# MCU.net
KiCad netlist of a schematic drawn in Altium Designer
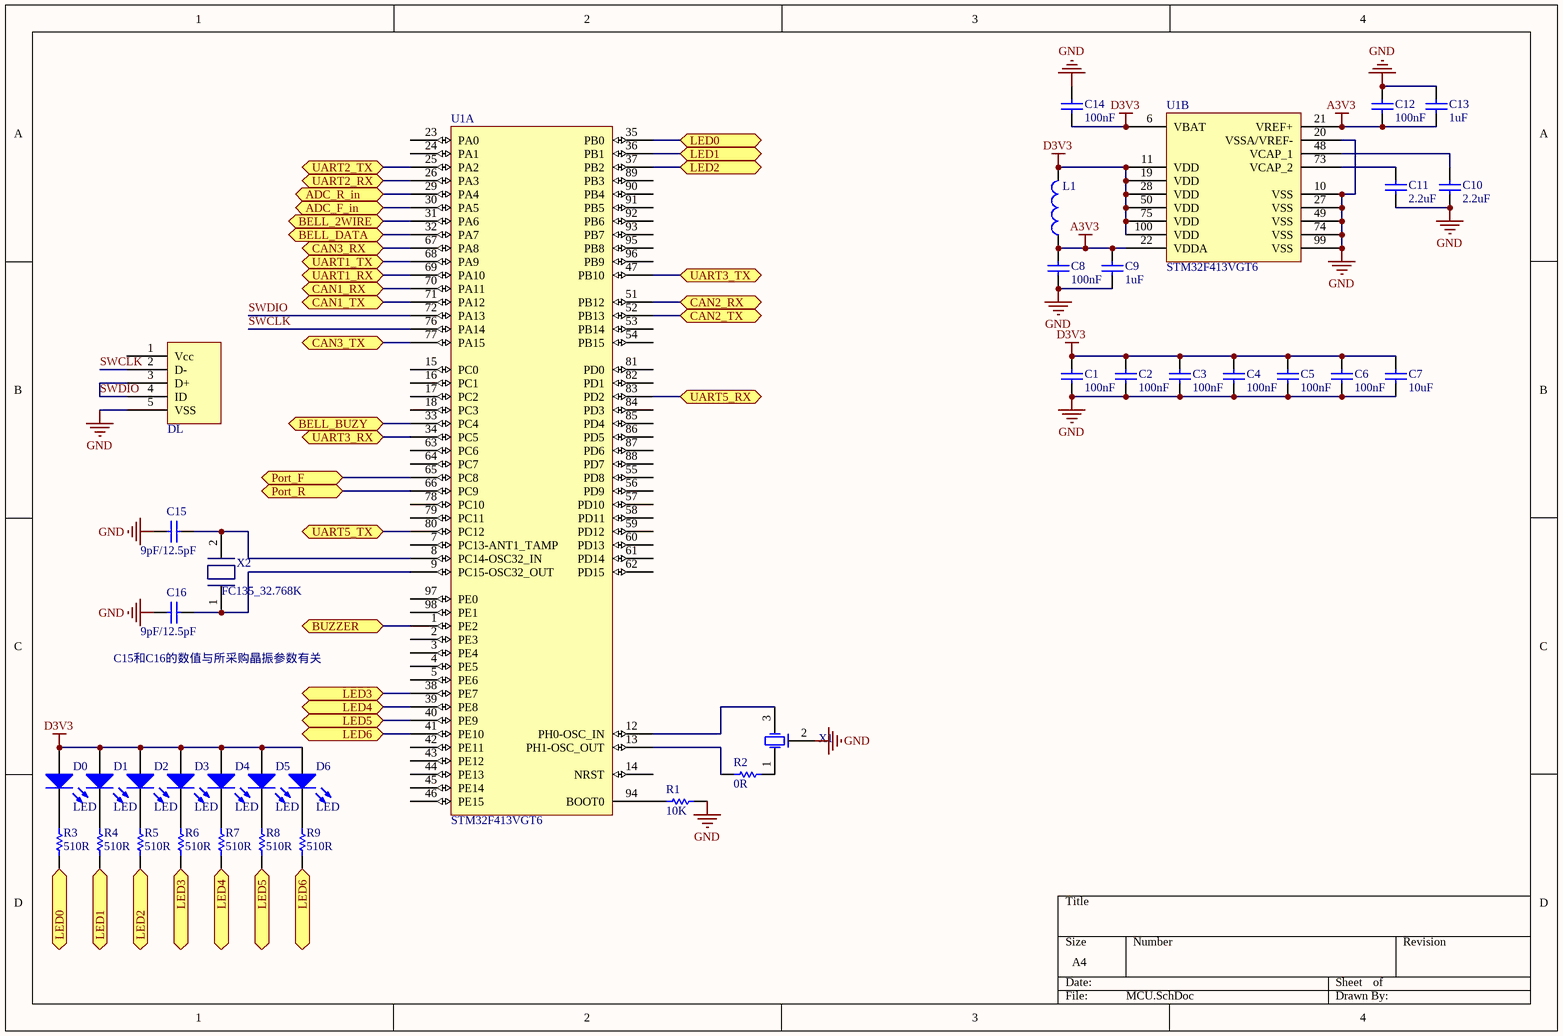
[diagram p0: MCU.SchDoc]

(export (version "E")
  (design (tool "Eeschema 10.0.6"))
  (components
    (comp (ref "C1")
      (value "100nF")
      (footprint "BinFeng:0402")
      (description "Capacitor")
      (fields (field (name "PUBLISHER") "Altium Limited"))
      (libsource (lib "Miscellaneous Devices") (part "Cap"))
    )
    (comp (ref "C2")
      (value "100nF")
      (footprint "BinFeng:0402")
      (description "Capacitor")
      (fields (field (name "PUBLISHER") "Altium Limited"))
      (libsource (lib "Miscellaneous Devices") (part "Cap"))
    )
    (comp (ref "C3")
      (value "100nF")
      (footprint "BinFeng:0402")
      (description "Capacitor")
      (fields (field (name "PUBLISHER") "Altium Limited"))
      (libsource (lib "Miscellaneous Devices") (part "Cap"))
    )
    (comp (ref "C4")
      (value "100nF")
      (footprint "BinFeng:0402")
      (description "Capacitor")
      (fields (field (name "PUBLISHER") "Altium Limited"))
      (libsource (lib "Miscellaneous Devices") (part "Cap"))
    )
    (comp (ref "C5")
      (value "100nF")
      (footprint "BinFeng:0402")
      (description "Capacitor")
      (fields (field (name "PUBLISHER") "Altium Limited"))
      (libsource (lib "Miscellaneous Devices") (part "Cap"))
    )
    (comp (ref "C6")
      (value "100nF")
      (footprint "BinFeng:0402")
      (description "Capacitor")
      (fields (field (name "PUBLISHER") "Altium Limited"))
      (libsource (lib "Miscellaneous Devices") (part "Cap"))
    )
    (comp (ref "C7")
      (value "10uF")
      (footprint "0805")
      (description "Capacitor")
      (fields (field (name "PUBLISHER") "Altium Limited"))
      (libsource (lib "Miscellaneous Devices") (part "Cap"))
    )
    (comp (ref "C8")
      (value "100nF")
      (footprint "BinFeng:0402")
      (description "Capacitor")
      (fields (field (name "PUBLISHER") "Altium Limited"))
      (libsource (lib "Miscellaneous Devices") (part "Cap"))
    )
    (comp (ref "C9")
      (value "1uF")
      (footprint "BinFeng:0402")
      (description "Capacitor")
      (fields (field (name "PUBLISHER") "Altium Limited"))
      (libsource (lib "Miscellaneous Devices") (part "Cap"))
    )
    (comp (ref "C10")
      (value "2.2uF")
      (footprint "BinFeng:0603")
      (description "Capacitor")
      (fields (field (name "PUBLISHER") "Altium Limited"))
      (libsource (lib "Miscellaneous Devices") (part "Cap"))
    )
    (comp (ref "C11")
      (value "2.2uF")
      (footprint "BinFeng:0603")
      (description "Capacitor")
      (fields (field (name "PUBLISHER") "Altium Limited"))
      (libsource (lib "Miscellaneous Devices") (part "Cap"))
    )
    (comp (ref "C12")
      (value "100nF")
      (footprint "BinFeng:0402")
      (description "Capacitor")
      (fields (field (name "PUBLISHER") "Altium Limited"))
      (libsource (lib "Miscellaneous Devices") (part "Cap"))
    )
    (comp (ref "C13")
      (value "1uF")
      (footprint "BinFeng:0402")
      (description "Capacitor")
      (fields (field (name "PUBLISHER") "Altium Limited"))
      (libsource (lib "Miscellaneous Devices") (part "Cap"))
    )
    (comp (ref "C14")
      (value "100nF")
      (footprint "BinFeng:0402")
      (description "Capacitor")
      (fields (field (name "PUBLISHER") "Altium Limited"))
      (libsource (lib "Miscellaneous Devices") (part "Cap"))
    )
    (comp (ref "C15")
      (value "9pF/12.5pF")
      (footprint "BinFeng:0402")
      (description "Capacitor")
      (fields (field (name "PUBLISHER") "Altium Limited"))
      (libsource (lib "Miscellaneous Devices") (part "Cap"))
    )
    (comp (ref "C16")
      (value "9pF/12.5pF")
      (footprint "BinFeng:0402")
      (description "Capacitor")
      (fields (field (name "PUBLISHER") "Altium Limited"))
      (libsource (lib "Miscellaneous Devices") (part "Cap"))
    )
    (comp (ref "D0")
      (value "LED")
      (footprint "1206")
      (description "green LED")
      (fields (field (name "PUBLISHER") "Altium Limited"))
      (libsource (lib "Miscellaneous Devices") (part "LED0"))
    )
    (comp (ref "D1")
      (value "LED")
      (footprint "1206")
      (description "green LED")
      (fields (field (name "PUBLISHER") "Altium Limited"))
      (libsource (lib "Miscellaneous Devices") (part "LED0"))
    )
    (comp (ref "D2")
      (value "LED")
      (footprint "1206")
      (description "green LED")
      (fields (field (name "PUBLISHER") "Altium Limited"))
      (libsource (lib "Miscellaneous Devices") (part "LED0"))
    )
    (comp (ref "D3")
      (value "LED")
      (footprint "1206")
      (description "green LED")
      (fields (field (name "PUBLISHER") "Altium Limited"))
      (libsource (lib "Miscellaneous Devices") (part "LED0"))
    )
    (comp (ref "D4")
      (value "LED")
      (footprint "1206")
      (description "green LED")
      (fields (field (name "PUBLISHER") "Altium Limited"))
      (libsource (lib "Miscellaneous Devices") (part "LED0"))
    )
    (comp (ref "D5")
      (value "LED")
      (footprint "1206")
      (description "green LED")
      (fields (field (name "PUBLISHER") "Altium Limited"))
      (libsource (lib "Miscellaneous Devices") (part "LED0"))
    )
    (comp (ref "D6")
      (value "LED")
      (footprint "1206")
      (description "green LED")
      (fields (field (name "PUBLISHER") "Altium Limited"))
      (libsource (lib "Miscellaneous Devices") (part "LED0"))
    )
    (comp (ref "DL")
      (value "USB_5pin")
      (footprint "USBmicro_B")
      (libsource (lib "BinFeng_Connectors") (part "USB_5pin"))
    )
    (comp (ref "L1")
      (value "BLM15BD221SN1D")
      (footprint "BinFeng:0402")
      (description "muRata ferrite bead")
      (fields (field (name "PUBLISHER") "Altium Limited"))
      (libsource (lib "Miscellaneous Devices") (part "Inductor"))
    )
    (comp (ref "R1")
      (value "10K")
      (footprint "BinFeng:0402")
      (description "Resistor")
      (fields (field (name "PUBLISHER") "Altium Limited"))
      (libsource (lib "Miscellaneous Devices") (part "Res1"))
    )
    (comp (ref "R2")
      (value "0R")
      (footprint "BinFeng:0402")
      (description "Resistor")
      (fields (field (name "PUBLISHER") "Altium Limited"))
      (libsource (lib "Miscellaneous Devices") (part "Res1"))
    )
    (comp (ref "R3")
      (value "510R")
      (footprint "BinFeng:0402")
      (description "Resistor")
      (fields (field (name "PUBLISHER") "Altium Limited"))
      (libsource (lib "Miscellaneous Devices") (part "Res1"))
    )
    (comp (ref "R4")
      (value "510R")
      (footprint "BinFeng:0402")
      (description "Resistor")
      (fields (field (name "PUBLISHER") "Altium Limited"))
      (libsource (lib "Miscellaneous Devices") (part "Res1"))
    )
    (comp (ref "R5")
      (value "510R")
      (footprint "BinFeng:0402")
      (description "Resistor")
      (fields (field (name "PUBLISHER") "Altium Limited"))
      (libsource (lib "Miscellaneous Devices") (part "Res1"))
    )
    (comp (ref "R6")
      (value "510R")
      (footprint "BinFeng:0402")
      (description "Resistor")
      (fields (field (name "PUBLISHER") "Altium Limited"))
      (libsource (lib "Miscellaneous Devices") (part "Res1"))
    )
    (comp (ref "R7")
      (value "510R")
      (footprint "BinFeng:0402")
      (description "Resistor")
      (fields (field (name "PUBLISHER") "Altium Limited"))
      (libsource (lib "Miscellaneous Devices") (part "Res1"))
    )
    (comp (ref "R8")
      (value "510R")
      (footprint "BinFeng:0402")
      (description "Resistor")
      (fields (field (name "PUBLISHER") "Altium Limited"))
      (libsource (lib "Miscellaneous Devices") (part "Res1"))
    )
    (comp (ref "R9")
      (value "510R")
      (footprint "BinFeng:0402")
      (description "Resistor")
      (fields (field (name "PUBLISHER") "Altium Limited"))
      (libsource (lib "Miscellaneous Devices") (part "Res1"))
    )
    (comp (ref "U1")
      (value "STM32F413VGT6")
      (footprint "STM-LQFP100_V")
      (description "ARM Cortex-M4 32-Bit DSP+FPU, 1024 KB Flash, 82 I/Os, 100-Pin LQFP, -40 to 85 degC, Tray")
      (libsource (lib "Altium Content Vault") (part "STM-STM32F413-LQFP-100"))
    )
    (comp (ref "X1")
      (value "8M smd")
      (footprint "8Mhz_XTAL")
      (description "muRata")
      (libsource (lib "Schlib1") (part "8M smd"))
    )
    (comp (ref "X2")
      (value "FC135_32.768K")
      (footprint "FC135")
      (libsource (lib "BinFeng_IC") (part "XTAL_32.768k"))
    )
  )
  (nets
    (net (code "1") (name "/ADC_F_in") (class "Default")
      (node (ref "U1") (pin "30") (pinfunction "PA5_30") (pintype "bidirectional"))
    )
    (net (code "2") (name "/ADC_R_in") (class "Default")
      (node (ref "U1") (pin "29") (pinfunction "PA4_29") (pintype "bidirectional"))
    )
    (net (code "3") (name "/BELL_2WIRE") (class "Default")
      (node (ref "U1") (pin "31") (pinfunction "PA6_31") (pintype "bidirectional"))
    )
    (net (code "4") (name "/BELL_BUZY") (class "Default")
      (node (ref "U1") (pin "33") (pinfunction "PC4_33") (pintype "bidirectional"))
    )
    (net (code "5") (name "/BELL_DATA") (class "Default")
      (node (ref "U1") (pin "32") (pinfunction "PA7_32") (pintype "bidirectional"))
    )
    (net (code "6") (name "/BUZZER") (class "Default")
      (node (ref "U1") (pin "1") (pinfunction "PE2_1") (pintype "bidirectional"))
    )
    (net (code "7") (name "/CAN1_RX") (class "Default")
      (node (ref "U1") (pin "70") (pinfunction "PA11_70") (pintype "bidirectional"))
    )
    (net (code "8") (name "/CAN1_TX") (class "Default")
      (node (ref "U1") (pin "71") (pinfunction "PA12_71") (pintype "bidirectional"))
    )
    (net (code "9") (name "/CAN2_RX") (class "Default")
      (node (ref "U1") (pin "51") (pinfunction "PB12_51") (pintype "bidirectional"))
    )
    (net (code "10") (name "/CAN2_TX") (class "Default")
      (node (ref "U1") (pin "52") (pinfunction "PB13_52") (pintype "bidirectional"))
    )
    (net (code "11") (name "/CAN3_RX") (class "Default")
      (node (ref "U1") (pin "67") (pinfunction "PA8_67") (pintype "bidirectional"))
    )
    (net (code "12") (name "/CAN3_TX") (class "Default")
      (node (ref "U1") (pin "77") (pinfunction "PA15_77") (pintype "bidirectional"))
    )
    (net (code "13") (name "/LED0") (class "Default")
      (node (ref "R3") (pin "1") (pinfunction "1_1") (pintype "passive"))
      (node (ref "U1") (pin "35") (pinfunction "PB0_35") (pintype "bidirectional"))
    )
    (net (code "14") (name "/LED1") (class "Default")
      (node (ref "R4") (pin "1") (pinfunction "1_1") (pintype "passive"))
      (node (ref "U1") (pin "36") (pinfunction "PB1_36") (pintype "bidirectional"))
    )
    (net (code "15") (name "/LED2") (class "Default")
      (node (ref "R5") (pin "1") (pinfunction "1_1") (pintype "passive"))
      (node (ref "U1") (pin "37") (pinfunction "PB2_37") (pintype "bidirectional"))
    )
    (net (code "16") (name "/LED3") (class "Default")
      (node (ref "R6") (pin "1") (pinfunction "1_1") (pintype "passive"))
      (node (ref "U1") (pin "38") (pinfunction "PE7_38") (pintype "bidirectional"))
    )
    (net (code "17") (name "/LED4") (class "Default")
      (node (ref "R7") (pin "1") (pinfunction "1_1") (pintype "passive"))
      (node (ref "U1") (pin "39") (pinfunction "PE8_39") (pintype "bidirectional"))
    )
    (net (code "18") (name "/LED5") (class "Default")
      (node (ref "R8") (pin "1") (pinfunction "1_1") (pintype "passive"))
      (node (ref "U1") (pin "40") (pinfunction "PE9_40") (pintype "bidirectional"))
    )
    (net (code "19") (name "/LED6") (class "Default")
      (node (ref "R9") (pin "1") (pinfunction "1_1") (pintype "passive"))
      (node (ref "U1") (pin "41") (pinfunction "PE10_41") (pintype "bidirectional"))
    )
    (net (code "20") (name "/Port_F") (class "Default")
      (node (ref "U1") (pin "65") (pinfunction "PC8_65") (pintype "bidirectional"))
    )
    (net (code "21") (name "/Port_R") (class "Default")
      (node (ref "U1") (pin "66") (pinfunction "PC9_66") (pintype "bidirectional"))
    )
    (net (code "22") (name "/SWCLK") (class "Default")
      (node (ref "DL") (pin "2") (pinfunction "D-_2") (pintype "passive"))
      (node (ref "U1") (pin "76") (pinfunction "PA14_76") (pintype "bidirectional"))
    )
    (net (code "23") (name "/SWDIO") (class "Default")
      (node (ref "DL") (pin "3") (pinfunction "D+_3") (pintype "passive"))
      (node (ref "DL") (pin "4") (pinfunction "ID_4") (pintype "passive"))
      (node (ref "U1") (pin "72") (pinfunction "PA13_72") (pintype "bidirectional"))
    )
    (net (code "24") (name "/UART1_RX") (class "Default")
      (node (ref "U1") (pin "69") (pinfunction "PA10_69") (pintype "bidirectional"))
    )
    (net (code "25") (name "/UART1_TX") (class "Default")
      (node (ref "U1") (pin "68") (pinfunction "PA9_68") (pintype "bidirectional"))
    )
    (net (code "26") (name "/UART2_RX") (class "Default")
      (node (ref "U1") (pin "26") (pinfunction "PA3_26") (pintype "bidirectional"))
    )
    (net (code "27") (name "/UART2_TX") (class "Default")
      (node (ref "U1") (pin "25") (pinfunction "PA2_25") (pintype "bidirectional"))
    )
    (net (code "28") (name "/UART3_RX") (class "Default")
      (node (ref "U1") (pin "34") (pinfunction "PC5_34") (pintype "bidirectional"))
    )
    (net (code "29") (name "/UART3_TX") (class "Default")
      (node (ref "U1") (pin "47") (pinfunction "PB10_47") (pintype "bidirectional"))
    )
    (net (code "30") (name "/UART5_RX") (class "Default")
      (node (ref "U1") (pin "83") (pinfunction "PD2_83") (pintype "bidirectional"))
    )
    (net (code "31") (name "/UART5_TX") (class "Default")
      (node (ref "U1") (pin "80") (pinfunction "PC12_80") (pintype "bidirectional"))
    )
    (net (code "32") (name "A3V3") (class "Default")
      (node (ref "C12") (pin "1") (pinfunction "1_1") (pintype "passive"))
      (node (ref "C13") (pin "1") (pinfunction "1_1") (pintype "passive"))
      (node (ref "C8") (pin "2") (pinfunction "2_2") (pintype "passive"))
      (node (ref "C9") (pin "2") (pinfunction "2_2") (pintype "passive"))
      (node (ref "L1") (pin "1") (pinfunction "1_1") (pintype "passive"))
      (node (ref "U1") (pin "21") (pinfunction "VREF+_21") (pintype "power_in"))
      (node (ref "U1") (pin "22") (pinfunction "VDDA_22") (pintype "power_in"))
    )
    (net (code "33") (name "D3V3") (class "Default")
      (node (ref "C1") (pin "2") (pinfunction "2_2") (pintype "passive"))
      (node (ref "C14") (pin "1") (pinfunction "1_1") (pintype "passive"))
      (node (ref "C2") (pin "2") (pinfunction "2_2") (pintype "passive"))
      (node (ref "C3") (pin "2") (pinfunction "2_2") (pintype "passive"))
      (node (ref "C4") (pin "2") (pinfunction "2_2") (pintype "passive"))
      (node (ref "C5") (pin "2") (pinfunction "2_2") (pintype "passive"))
      (node (ref "C6") (pin "2") (pinfunction "2_2") (pintype "passive"))
      (node (ref "C7") (pin "2") (pinfunction "2_2") (pintype "passive"))
      (node (ref "D0") (pin "1") (pinfunction "A_1") (pintype "passive"))
      (node (ref "D1") (pin "1") (pinfunction "A_1") (pintype "passive"))
      (node (ref "D2") (pin "1") (pinfunction "A_1") (pintype "passive"))
      (node (ref "D3") (pin "1") (pinfunction "A_1") (pintype "passive"))
      (node (ref "D4") (pin "1") (pinfunction "A_1") (pintype "passive"))
      (node (ref "D5") (pin "1") (pinfunction "A_1") (pintype "passive"))
      (node (ref "D6") (pin "1") (pinfunction "A_1") (pintype "passive"))
      (node (ref "L1") (pin "2") (pinfunction "2_2") (pintype "passive"))
      (node (ref "U1") (pin "100") (pinfunction "VDD_100") (pintype "power_in"))
      (node (ref "U1") (pin "11") (pinfunction "VDD_11") (pintype "power_in"))
      (node (ref "U1") (pin "19") (pinfunction "VDD_19") (pintype "power_in"))
      (node (ref "U1") (pin "28") (pinfunction "VDD_28") (pintype "power_in"))
      (node (ref "U1") (pin "50") (pinfunction "VDD_50") (pintype "power_in"))
      (node (ref "U1") (pin "6") (pinfunction "VBAT_6") (pintype "power_in"))
      (node (ref "U1") (pin "75") (pinfunction "VDD_75") (pintype "power_in"))
    )
    (net (code "34") (name "GND") (class "Default")
      (node (ref "C1") (pin "1") (pinfunction "1_1") (pintype "passive"))
      (node (ref "C10") (pin "1") (pinfunction "1_1") (pintype "passive"))
      (node (ref "C11") (pin "1") (pinfunction "1_1") (pintype "passive"))
      (node (ref "C12") (pin "2") (pinfunction "2_2") (pintype "passive"))
      (node (ref "C13") (pin "2") (pinfunction "2_2") (pintype "passive"))
      (node (ref "C14") (pin "2") (pinfunction "2_2") (pintype "passive"))
      (node (ref "C15") (pin "2") (pinfunction "2_2") (pintype "passive"))
      (node (ref "C16") (pin "2") (pinfunction "2_2") (pintype "passive"))
      (node (ref "C2") (pin "1") (pinfunction "1_1") (pintype "passive"))
      (node (ref "C3") (pin "1") (pinfunction "1_1") (pintype "passive"))
      (node (ref "C4") (pin "1") (pinfunction "1_1") (pintype "passive"))
      (node (ref "C5") (pin "1") (pinfunction "1_1") (pintype "passive"))
      (node (ref "C6") (pin "1") (pinfunction "1_1") (pintype "passive"))
      (node (ref "C7") (pin "1") (pinfunction "1_1") (pintype "passive"))
      (node (ref "C8") (pin "1") (pinfunction "1_1") (pintype "passive"))
      (node (ref "C9") (pin "1") (pinfunction "1_1") (pintype "passive"))
      (node (ref "DL") (pin "5") (pinfunction "VSS_5") (pintype "passive"))
      (node (ref "R1") (pin "2") (pinfunction "2_2") (pintype "passive"))
      (node (ref "U1") (pin "10") (pinfunction "VSS_10") (pintype "power_in"))
      (node (ref "U1") (pin "20") (pinfunction "VSSA/VREF-_20") (pintype "power_in"))
      (node (ref "U1") (pin "27") (pinfunction "VSS_27") (pintype "power_in"))
      (node (ref "U1") (pin "49") (pinfunction "VSS_49") (pintype "power_in"))
      (node (ref "U1") (pin "74") (pinfunction "VSS_74") (pintype "power_in"))
      (node (ref "U1") (pin "99") (pinfunction "VSS_99") (pintype "power_in"))
      (node (ref "X1") (pin "2") (pinfunction "GND_2") (pintype "passive"))
    )
    (net (code "35") (name "Net-(D0-K)") (class "Default")
      (node (ref "D0") (pin "2") (pinfunction "K_2") (pintype "passive"))
      (node (ref "R3") (pin "2") (pinfunction "2_2") (pintype "passive"))
    )
    (net (code "36") (name "Net-(D1-K)") (class "Default")
      (node (ref "D1") (pin "2") (pinfunction "K_2") (pintype "passive"))
      (node (ref "R4") (pin "2") (pinfunction "2_2") (pintype "passive"))
    )
    (net (code "37") (name "Net-(D2-K)") (class "Default")
      (node (ref "D2") (pin "2") (pinfunction "K_2") (pintype "passive"))
      (node (ref "R5") (pin "2") (pinfunction "2_2") (pintype "passive"))
    )
    (net (code "38") (name "Net-(D3-K)") (class "Default")
      (node (ref "D3") (pin "2") (pinfunction "K_2") (pintype "passive"))
      (node (ref "R6") (pin "2") (pinfunction "2_2") (pintype "passive"))
    )
    (net (code "39") (name "Net-(D4-K)") (class "Default")
      (node (ref "D4") (pin "2") (pinfunction "K_2") (pintype "passive"))
      (node (ref "R7") (pin "2") (pinfunction "2_2") (pintype "passive"))
    )
    (net (code "40") (name "Net-(D5-K)") (class "Default")
      (node (ref "D5") (pin "2") (pinfunction "K_2") (pintype "passive"))
      (node (ref "R8") (pin "2") (pinfunction "2_2") (pintype "passive"))
    )
    (net (code "41") (name "Net-(D6-K)") (class "Default")
      (node (ref "D6") (pin "2") (pinfunction "K_2") (pintype "passive"))
      (node (ref "R9") (pin "2") (pinfunction "2_2") (pintype "passive"))
    )
    (net (code "42") (name "Net-(U1A-BOOT0)") (class "Default")
      (node (ref "R1") (pin "1") (pinfunction "1_1") (pintype "passive"))
      (node (ref "U1") (pin "94") (pinfunction "BOOT0_94") (pintype "passive"))
    )
    (net (code "43") (name "Net-(U1A-PC14-OSC32_IN)") (class "Default")
      (node (ref "C15") (pin "1") (pinfunction "1_1") (pintype "passive"))
      (node (ref "U1") (pin "8") (pinfunction "PC14-OSC32_IN_8") (pintype "bidirectional"))
      (node (ref "X2") (pin "2") (pinfunction "2_2") (pintype "passive"))
    )
    (net (code "44") (name "Net-(U1A-PC15-OSC32_OUT)") (class "Default")
      (node (ref "C16") (pin "1") (pinfunction "1_1") (pintype "passive"))
      (node (ref "U1") (pin "9") (pinfunction "PC15-OSC32_OUT_9") (pintype "bidirectional"))
      (node (ref "X2") (pin "1") (pinfunction "1_1") (pintype "passive"))
    )
    (net (code "45") (name "Net-(U1A-PH0-OSC_IN)") (class "Default")
      (node (ref "U1") (pin "12") (pinfunction "PH0-OSC_IN_12") (pintype "bidirectional"))
      (node (ref "X1") (pin "3") (pinfunction "OSC2_3") (pintype "passive"))
    )
    (net (code "46") (name "Net-(U1A-PH1-OSC_OUT)") (class "Default")
      (node (ref "R2") (pin "2") (pinfunction "2_2") (pintype "passive"))
      (node (ref "U1") (pin "13") (pinfunction "PH1-OSC_OUT_13") (pintype "bidirectional"))
    )
    (net (code "47") (name "Net-(U1B-VCAP_1)") (class "Default")
      (node (ref "C10") (pin "2") (pinfunction "2_2") (pintype "passive"))
      (node (ref "U1") (pin "48") (pinfunction "VCAP_1_48") (pintype "passive"))
    )
    (net (code "48") (name "Net-(U1B-VCAP_2)") (class "Default")
      (node (ref "C11") (pin "2") (pinfunction "2_2") (pintype "passive"))
      (node (ref "U1") (pin "73") (pinfunction "VCAP_2_73") (pintype "passive"))
    )
    (net (code "49") (name "Net-(X1-OSC1)") (class "Default")
      (node (ref "R2") (pin "1") (pinfunction "1_1") (pintype "passive"))
      (node (ref "X1") (pin "1") (pinfunction "OSC1_1") (pintype "passive"))
    )
    (net (code "50") (name "unconnected-(DL-Vcc-Pad1)") (class "Default")
      (node (ref "DL") (pin "1") (pinfunction "Vcc_1") (pintype "passive"))
    )
    (net (code "51") (name "unconnected-(U1A-NRST-Pad14)") (class "Default")
      (node (ref "U1") (pin "14") (pinfunction "NRST_14") (pintype "bidirectional"))
    )
    (net (code "52") (name "unconnected-(U1A-PA0-Pad23)") (class "Default")
      (node (ref "U1") (pin "23") (pinfunction "PA0_23") (pintype "bidirectional"))
    )
    (net (code "53") (name "unconnected-(U1A-PA1-Pad24)") (class "Default")
      (node (ref "U1") (pin "24") (pinfunction "PA1_24") (pintype "bidirectional"))
    )
    (net (code "54") (name "unconnected-(U1A-PB3-Pad89)") (class "Default")
      (node (ref "U1") (pin "89") (pinfunction "PB3_89") (pintype "bidirectional"))
    )
    (net (code "55") (name "unconnected-(U1A-PB4-Pad90)") (class "Default")
      (node (ref "U1") (pin "90") (pinfunction "PB4_90") (pintype "bidirectional"))
    )
    (net (code "56") (name "unconnected-(U1A-PB5-Pad91)") (class "Default")
      (node (ref "U1") (pin "91") (pinfunction "PB5_91") (pintype "bidirectional"))
    )
    (net (code "57") (name "unconnected-(U1A-PB6-Pad92)") (class "Default")
      (node (ref "U1") (pin "92") (pinfunction "PB6_92") (pintype "bidirectional"))
    )
    (net (code "58") (name "unconnected-(U1A-PB7-Pad93)") (class "Default")
      (node (ref "U1") (pin "93") (pinfunction "PB7_93") (pintype "bidirectional"))
    )
    (net (code "59") (name "unconnected-(U1A-PB8-Pad95)") (class "Default")
      (node (ref "U1") (pin "95") (pinfunction "PB8_95") (pintype "bidirectional"))
    )
    (net (code "60") (name "unconnected-(U1A-PB9-Pad96)") (class "Default")
      (node (ref "U1") (pin "96") (pinfunction "PB9_96") (pintype "bidirectional"))
    )
    (net (code "61") (name "unconnected-(U1A-PB14-Pad53)") (class "Default")
      (node (ref "U1") (pin "53") (pinfunction "PB14_53") (pintype "bidirectional"))
    )
    (net (code "62") (name "unconnected-(U1A-PB15-Pad54)") (class "Default")
      (node (ref "U1") (pin "54") (pinfunction "PB15_54") (pintype "bidirectional"))
    )
    (net (code "63") (name "unconnected-(U1A-PC0-Pad15)") (class "Default")
      (node (ref "U1") (pin "15") (pinfunction "PC0_15") (pintype "bidirectional"))
    )
    (net (code "64") (name "unconnected-(U1A-PC1-Pad16)") (class "Default")
      (node (ref "U1") (pin "16") (pinfunction "PC1_16") (pintype "bidirectional"))
    )
    (net (code "65") (name "unconnected-(U1A-PC2-Pad17)") (class "Default")
      (node (ref "U1") (pin "17") (pinfunction "PC2_17") (pintype "bidirectional"))
    )
    (net (code "66") (name "unconnected-(U1A-PC3-Pad18)") (class "Default")
      (node (ref "U1") (pin "18") (pinfunction "PC3_18") (pintype "bidirectional"))
    )
    (net (code "67") (name "unconnected-(U1A-PC6-Pad63)") (class "Default")
      (node (ref "U1") (pin "63") (pinfunction "PC6_63") (pintype "bidirectional"))
    )
    (net (code "68") (name "unconnected-(U1A-PC7-Pad64)") (class "Default")
      (node (ref "U1") (pin "64") (pinfunction "PC7_64") (pintype "bidirectional"))
    )
    (net (code "69") (name "unconnected-(U1A-PC10-Pad78)") (class "Default")
      (node (ref "U1") (pin "78") (pinfunction "PC10_78") (pintype "bidirectional"))
    )
    (net (code "70") (name "unconnected-(U1A-PC11-Pad79)") (class "Default")
      (node (ref "U1") (pin "79") (pinfunction "PC11_79") (pintype "bidirectional"))
    )
    (net (code "71") (name "unconnected-(U1A-PC13-ANT1_TAMP-Pad7)") (class "Default")
      (node (ref "U1") (pin "7") (pinfunction "PC13-ANT1_TAMP_7") (pintype "bidirectional"))
    )
    (net (code "72") (name "unconnected-(U1A-PD0-Pad81)") (class "Default")
      (node (ref "U1") (pin "81") (pinfunction "PD0_81") (pintype "bidirectional"))
    )
    (net (code "73") (name "unconnected-(U1A-PD1-Pad82)") (class "Default")
      (node (ref "U1") (pin "82") (pinfunction "PD1_82") (pintype "bidirectional"))
    )
    (net (code "74") (name "unconnected-(U1A-PD3-Pad84)") (class "Default")
      (node (ref "U1") (pin "84") (pinfunction "PD3_84") (pintype "bidirectional"))
    )
    (net (code "75") (name "unconnected-(U1A-PD4-Pad85)") (class "Default")
      (node (ref "U1") (pin "85") (pinfunction "PD4_85") (pintype "bidirectional"))
    )
    (net (code "76") (name "unconnected-(U1A-PD5-Pad86)") (class "Default")
      (node (ref "U1") (pin "86") (pinfunction "PD5_86") (pintype "bidirectional"))
    )
    (net (code "77") (name "unconnected-(U1A-PD6-Pad87)") (class "Default")
      (node (ref "U1") (pin "87") (pinfunction "PD6_87") (pintype "bidirectional"))
    )
    (net (code "78") (name "unconnected-(U1A-PD7-Pad88)") (class "Default")
      (node (ref "U1") (pin "88") (pinfunction "PD7_88") (pintype "bidirectional"))
    )
    (net (code "79") (name "unconnected-(U1A-PD8-Pad55)") (class "Default")
      (node (ref "U1") (pin "55") (pinfunction "PD8_55") (pintype "bidirectional"))
    )
    (net (code "80") (name "unconnected-(U1A-PD9-Pad56)") (class "Default")
      (node (ref "U1") (pin "56") (pinfunction "PD9_56") (pintype "bidirectional"))
    )
    (net (code "81") (name "unconnected-(U1A-PD10-Pad57)") (class "Default")
      (node (ref "U1") (pin "57") (pinfunction "PD10_57") (pintype "bidirectional"))
    )
    (net (code "82") (name "unconnected-(U1A-PD11-Pad58)") (class "Default")
      (node (ref "U1") (pin "58") (pinfunction "PD11_58") (pintype "bidirectional"))
    )
    (net (code "83") (name "unconnected-(U1A-PD12-Pad59)") (class "Default")
      (node (ref "U1") (pin "59") (pinfunction "PD12_59") (pintype "bidirectional"))
    )
    (net (code "84") (name "unconnected-(U1A-PD13-Pad60)") (class "Default")
      (node (ref "U1") (pin "60") (pinfunction "PD13_60") (pintype "bidirectional"))
    )
    (net (code "85") (name "unconnected-(U1A-PD14-Pad61)") (class "Default")
      (node (ref "U1") (pin "61") (pinfunction "PD14_61") (pintype "bidirectional"))
    )
    (net (code "86") (name "unconnected-(U1A-PD15-Pad62)") (class "Default")
      (node (ref "U1") (pin "62") (pinfunction "PD15_62") (pintype "bidirectional"))
    )
    (net (code "87") (name "unconnected-(U1A-PE0-Pad97)") (class "Default")
      (node (ref "U1") (pin "97") (pinfunction "PE0_97") (pintype "bidirectional"))
    )
    (net (code "88") (name "unconnected-(U1A-PE1-Pad98)") (class "Default")
      (node (ref "U1") (pin "98") (pinfunction "PE1_98") (pintype "bidirectional"))
    )
    (net (code "89") (name "unconnected-(U1A-PE3-Pad2)") (class "Default")
      (node (ref "U1") (pin "2") (pinfunction "PE3_2") (pintype "bidirectional"))
    )
    (net (code "90") (name "unconnected-(U1A-PE4-Pad3)") (class "Default")
      (node (ref "U1") (pin "3") (pinfunction "PE4_3") (pintype "bidirectional"))
    )
    (net (code "91") (name "unconnected-(U1A-PE5-Pad4)") (class "Default")
      (node (ref "U1") (pin "4") (pinfunction "PE5_4") (pintype "bidirectional"))
    )
    (net (code "92") (name "unconnected-(U1A-PE6-Pad5)") (class "Default")
      (node (ref "U1") (pin "5") (pinfunction "PE6_5") (pintype "bidirectional"))
    )
    (net (code "93") (name "unconnected-(U1A-PE11-Pad42)") (class "Default")
      (node (ref "U1") (pin "42") (pinfunction "PE11_42") (pintype "bidirectional"))
    )
    (net (code "94") (name "unconnected-(U1A-PE12-Pad43)") (class "Default")
      (node (ref "U1") (pin "43") (pinfunction "PE12_43") (pintype "bidirectional"))
    )
    (net (code "95") (name "unconnected-(U1A-PE13-Pad44)") (class "Default")
      (node (ref "U1") (pin "44") (pinfunction "PE13_44") (pintype "bidirectional"))
    )
    (net (code "96") (name "unconnected-(U1A-PE14-Pad45)") (class "Default")
      (node (ref "U1") (pin "45") (pinfunction "PE14_45") (pintype "bidirectional"))
    )
    (net (code "97") (name "unconnected-(U1A-PE15-Pad46)") (class "Default")
      (node (ref "U1") (pin "46") (pinfunction "PE15_46") (pintype "bidirectional"))
    )
  )
)
